# schematic.net
KiCad netlist of a schematic drawn in EAGLE
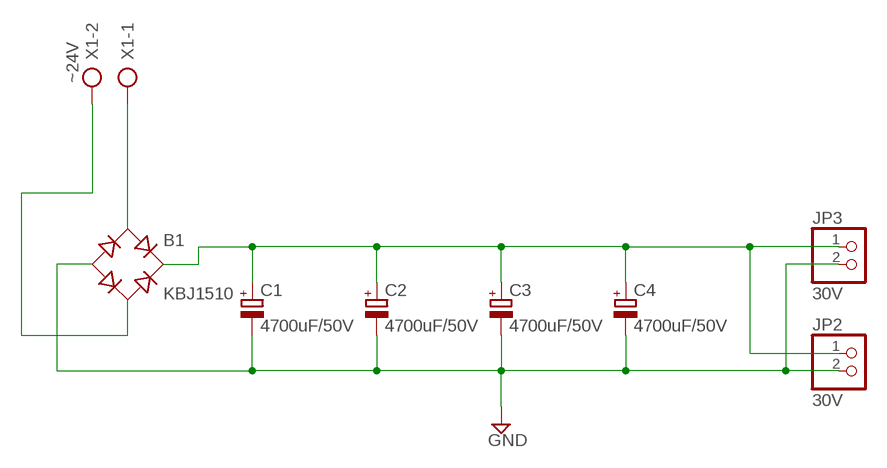
[diagram p0: schematic, sheet 1]

(export (version "E")
  (design (tool "Eeschema 10.0.6"))
  (components
    (comp (ref "B1")
      (value "KBJ1510")
      (footprint "eagle-import:FB32")
      (libsource (lib "eagle-import") (part "RECTIFIER-FB32"))
    )
    (comp (ref "C1")
      (value "4700uF/50V")
      (footprint "eagle-import:EB20D")
      (libsource (lib "eagle-import") (part "CPOL-EUE10-20"))
    )
    (comp (ref "C2")
      (value "4700uF/50V")
      (footprint "eagle-import:EB20D")
      (libsource (lib "eagle-import") (part "CPOL-EUE10-20"))
    )
    (comp (ref "C3")
      (value "4700uF/50V")
      (footprint "eagle-import:EB20D")
      (libsource (lib "eagle-import") (part "CPOL-EUE10-20"))
    )
    (comp (ref "C4")
      (value "4700uF/50V")
      (footprint "eagle-import:EB20D")
      (libsource (lib "eagle-import") (part "CPOL-EUE10-20"))
    )
    (comp (ref "JP2")
      (value "30V")
      (footprint "eagle-import:1X02")
      (libsource (lib "eagle-import") (part "PINHD-1X2"))
    )
    (comp (ref "JP3")
      (value "30V")
      (footprint "eagle-import:1X02")
      (libsource (lib "eagle-import") (part "PINHD-1X2"))
    )
    (comp (ref "X1")
      (value "~24V")
      (footprint "eagle-import:AK500_2")
      (libsource (lib "eagle-import") (part "AK500/2"))
    )
  )
  (nets
    (net (code "1") (name "GND") (class "Default")
      (node (ref "B1") (pin "-") (pinfunction "-_-") (pintype "passive"))
      (node (ref "C1") (pin "-") (pinfunction "-_-") (pintype "passive"))
      (node (ref "C2") (pin "-") (pinfunction "-_-") (pintype "passive"))
      (node (ref "C3") (pin "-") (pinfunction "-_-") (pintype "passive"))
      (node (ref "C4") (pin "-") (pinfunction "-_-") (pintype "passive"))
      (node (ref "JP2") (pin "2") (pinfunction "2_2") (pintype "passive"))
      (node (ref "JP3") (pin "2") (pinfunction "2_2") (pintype "passive"))
    )
    (net (code "2") (name "Net-(B1-Pad+)") (class "Default")
      (node (ref "B1") (pin "+") (pinfunction "+_+") (pintype "passive"))
      (node (ref "C1") (pin "+") (pinfunction "+_+") (pintype "passive"))
      (node (ref "C2") (pin "+") (pinfunction "+_+") (pintype "passive"))
      (node (ref "C3") (pin "+") (pinfunction "+_+") (pintype "passive"))
      (node (ref "C4") (pin "+") (pinfunction "+_+") (pintype "passive"))
      (node (ref "JP2") (pin "1") (pinfunction "1_1") (pintype "passive"))
      (node (ref "JP3") (pin "1") (pinfunction "1_1") (pintype "passive"))
    )
    (net (code "3") (name "Net-(X1A-KL)") (class "Default")
      (node (ref "B1") (pin "AC1") (pinfunction "AC1_AC1") (pintype "passive"))
      (node (ref "X1") (pin "1") (pinfunction "KL_1") (pintype "passive"))
    )
    (net (code "4") (name "Net-(X1B-KL)") (class "Default")
      (node (ref "B1") (pin "AC2") (pinfunction "AC2_AC2") (pintype "passive"))
      (node (ref "X1") (pin "2") (pinfunction "KL_2") (pintype "passive"))
    )
  )
)
